# CAN_RS232.net
KiCad netlist of a schematic drawn in Altium Designer
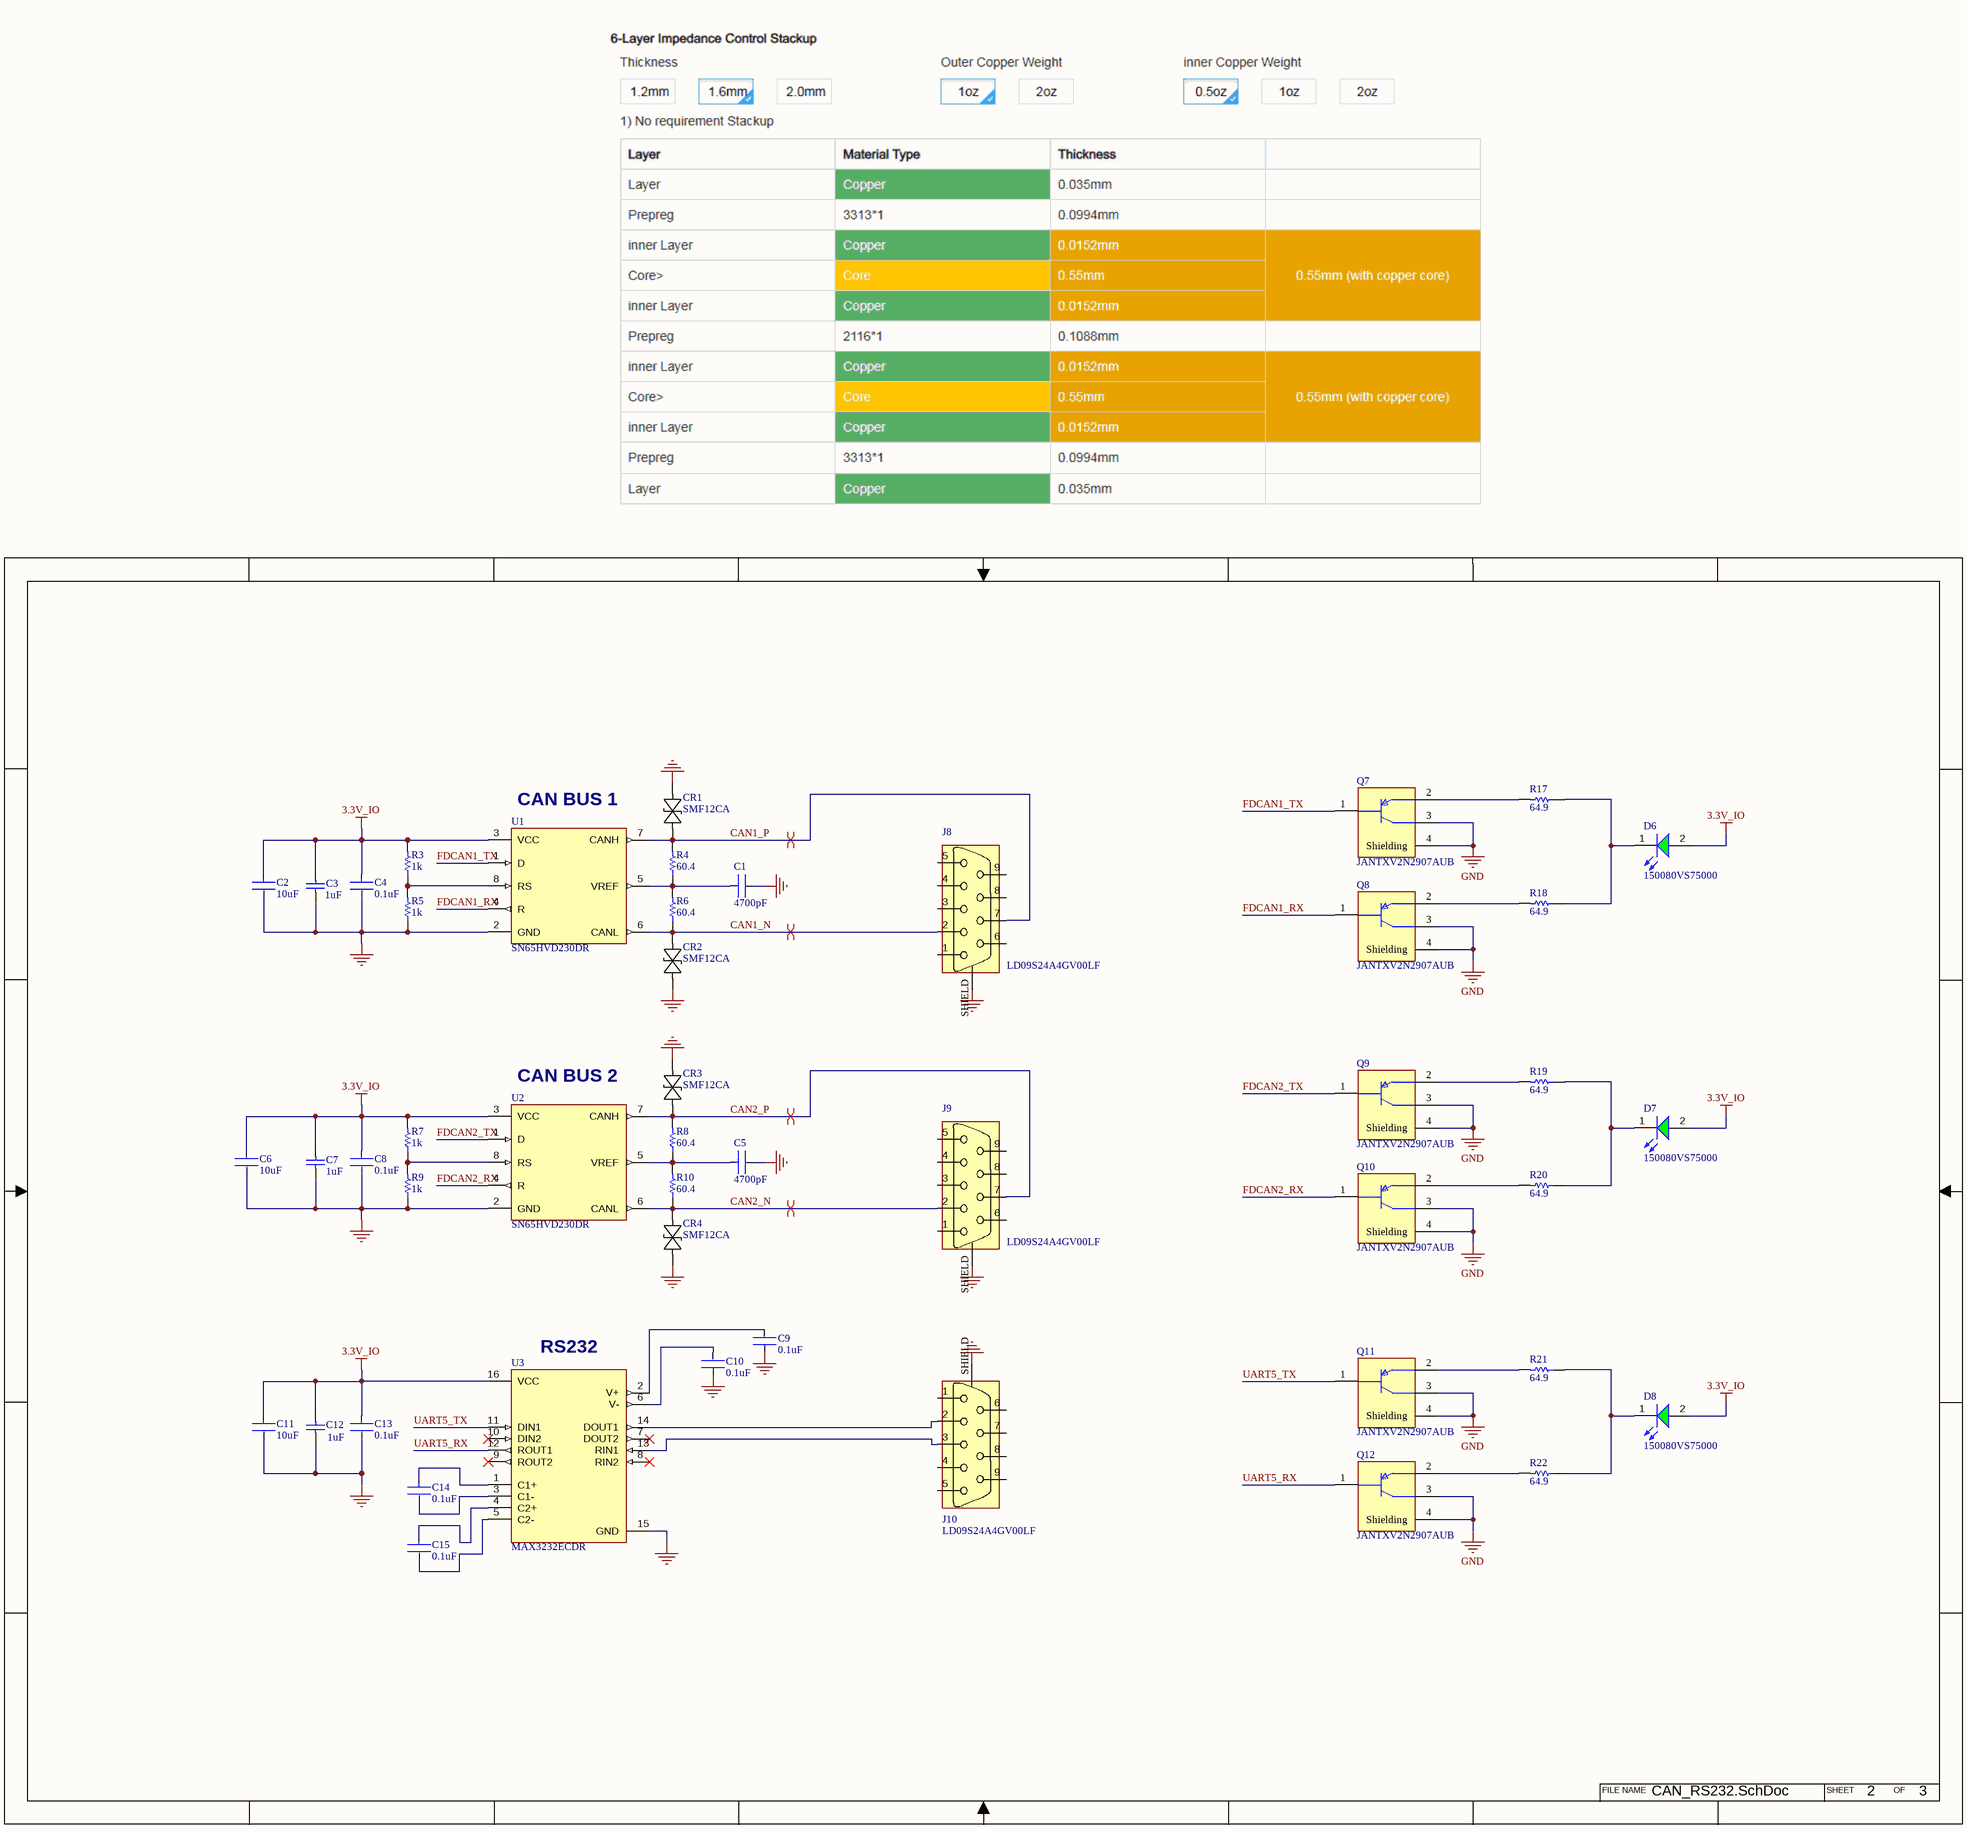
[diagram p0: CAN_RS232.SchDoc]

(export (version "E")
  (design (tool "Eeschema 10.0.6"))
  (components
    (comp (ref "C1")
      (value "4700pF")
      (footprint "FP-CC0805-0_85-MFG")
      (description "CAP CER 4700PF 50V X7R 0805")
      (fields (field (name "TOLERANCE") "0.1") (field (name "MANUFACTURER") "Yageo"))
      (libsource (lib "Altium Content Vault") (part "11868f565c42a9108669ba33697ecf6"))
    )
    (comp (ref "C2")
      (value "10uF")
      (footprint "FP-CL31-IPC_B")
      (description "Cap Ceramic 10uF 25V X7R ±10% SMD 1206 +125°C Embossed T/R")
      (fields (field (name "TOLERANCE") "10%"))
      (libsource (lib "Altium Content Vault") (part "b4654b650e69147ec39a6b967a45e02"))
    )
    (comp (ref "C3")
      (value "1uF")
      (footprint "CAPC2013X100X50ML20T25")
      (description "C0805C105K8RACTU")
      (fields (field (name "MANUFACTURER") "Kemet"))
      (libsource (lib "Altium Content Vault") (part "CAP"))
    )
    (comp (ref "C4")
      (value "0.1uF")
      (footprint "FP-CC0805-0_85-MFG")
      (description "CAP CER 0.1UF 50V X7R 0805")
      (fields (field (name "TOLERANCE") "0.1") (field (name "MANUFACTURER PART NUMBER") "CC0805KRX7R9BB104"))
      (libsource (lib "Altium Content Vault") (part "11868f565c42a9108669ba33697ecf6"))
    )
    (comp (ref "C5")
      (value "4700pF")
      (footprint "FP-CC0805-0_85-MFG")
      (description "CAP CER 4700PF 50V X7R 0805")
      (fields (field (name "TOLERANCE") "0.1") (field (name "MANUFACTURER") "Yageo"))
      (libsource (lib "Altium Content Vault") (part "11868f565c42a9108669ba33697ecf6"))
    )
    (comp (ref "C6")
      (value "10uF")
      (footprint "FP-CL31-IPC_B")
      (description "Cap Ceramic 10uF 25V X7R ±10% SMD 1206 +125°C Embossed T/R")
      (fields (field (name "TOLERANCE") "10%"))
      (libsource (lib "Altium Content Vault") (part "b4654b650e69147ec39a6b967a45e02"))
    )
    (comp (ref "C7")
      (value "1uF")
      (footprint "CAPC2013X100X50ML20T25")
      (fields (field (name "PART NUMBER") "C0805C105K8RACTU") (field (name "MANUFACTURER") "Kemet"))
      (libsource (lib "Altium Content Vault") (part "CAP"))
    )
    (comp (ref "C8")
      (value "0.1uF")
      (footprint "FP-CC0805-0_85-MFG")
      (description "CAP CER 0.1UF 50V X7R 0805")
      (fields (field (name "TOLERANCE") "0.1") (field (name "MANUFACTURER PART NUMBER") "CC0805KRX7R9BB104"))
      (libsource (lib "Altium Content Vault") (part "11868f565c42a9108669ba33697ecf6"))
    )
    (comp (ref "C9")
      (value "0.1uF")
      (footprint "FP-CC0805-0_85-MFG")
      (description "CAP CER 0.1UF 50V X7R 0805")
      (fields (field (name "TOLERANCE") "0.1") (field (name "MANUFACTURER PART NUMBER") "CC0805KRX7R9BB104"))
      (libsource (lib "Altium Content Vault") (part "11868f565c42a9108669ba33697ecf6"))
    )
    (comp (ref "C10")
      (value "0.1uF")
      (footprint "FP-CC0805-0_85-MFG")
      (description "CAP CER 0.1UF 50V X7R 0805")
      (fields (field (name "TOLERANCE") "0.1") (field (name "MANUFACTURER PART NUMBER") "CC0805KRX7R9BB104"))
      (libsource (lib "Altium Content Vault") (part "11868f565c42a9108669ba33697ecf6"))
    )
    (comp (ref "C11")
      (value "10uF")
      (footprint "FP-CL31-IPC_B")
      (description "Cap Ceramic 10uF 25V X7R ±10% SMD 1206 +125°C Embossed T/R")
      (fields (field (name "TOLERANCE") "10%"))
      (libsource (lib "Altium Content Vault") (part "b4654b650e69147ec39a6b967a45e02"))
    )
    (comp (ref "C12")
      (value "1uF")
      (footprint "CAPC2013X100X50ML20T25")
      (fields (field (name "PART NUMBER") "C0805C105K8RACTU") (field (name "MANUFACTURER") "Kemet"))
      (libsource (lib "Altium Content Vault") (part "CAP"))
    )
    (comp (ref "C13")
      (value "0.1uF")
      (footprint "FP-CC0805-0_85-MFG")
      (description "CAP CER 0.1UF 50V X7R 0805")
      (fields (field (name "TOLERANCE") "0.1") (field (name "MANUFACTURER PART NUMBER") "CC0805KRX7R9BB104"))
      (libsource (lib "Altium Content Vault") (part "11868f565c42a9108669ba33697ecf6"))
    )
    (comp (ref "C14")
      (value "0.1uF")
      (footprint "FP-CC0805-0_85-MFG")
      (description "CAP CER 0.1UF 50V X7R 0805")
      (fields (field (name "TOLERANCE") "0.1") (field (name "MANUFACTURER PART NUMBER") "CC0805KRX7R9BB104"))
      (libsource (lib "Altium Content Vault") (part "11868f565c42a9108669ba33697ecf6"))
    )
    (comp (ref "C15")
      (value "0.1uF")
      (footprint "FP-CC0805-0_85-MFG")
      (description "CAP CER 0.1UF 50V X7R 0805")
      (fields (field (name "TOLERANCE") "0.1") (field (name "MANUFACTURER PART NUMBER") "CC0805KRX7R9BB104"))
      (libsource (lib "Altium Content Vault") (part "11868f565c42a9108669ba33697ecf6"))
    )
    (comp (ref "CR1")
      (value "SMF12CA")
      (footprint "SOD-123F_LTF")
      (description "No Description Available")
      (libsource (lib "SMF12CA") (part "SMF12CA"))
    )
    (comp (ref "CR2")
      (value "SMF12CA")
      (footprint "SOD-123F_LTF")
      (description "No Description Available")
      (libsource (lib "SMF12CA") (part "SMF12CA"))
    )
    (comp (ref "CR3")
      (value "SMF12CA")
      (footprint "SOD-123F_LTF")
      (description "No Description Available")
      (libsource (lib "SMF12CA") (part "SMF12CA"))
    )
    (comp (ref "CR4")
      (value "SMF12CA")
      (footprint "SOD-123F_LTF")
      (description "No Description Available")
      (libsource (lib "SMF12CA") (part "SMF12CA"))
    )
    (comp (ref "D6")
      (value "150080VS75000")
      (footprint "WL-SMCW_0805_150080xx75000")
      (description "WL-SMCW SMT Mono-Color Chip LED Waterclear")
      (libsource (lib "Altium Content Vault") (part "LED_Green_2A-1K"))
    )
    (comp (ref "D7")
      (value "150080VS75000")
      (footprint "WL-SMCW_0805_150080xx75000")
      (description "WL-SMCW SMT Mono-Color Chip LED Waterclear")
      (libsource (lib "Altium Content Vault") (part "LED_Green_2A-1K"))
    )
    (comp (ref "D8")
      (value "150080VS75000")
      (footprint "WL-SMCW_0805_150080xx75000")
      (description "WL-SMCW SMT Mono-Color Chip LED Waterclear")
      (libsource (lib "Altium Content Vault") (part "LED_Green_2A-1K"))
    )
    (comp (ref "J8")
      (value "LD09S24A4GV00LF")
      (footprint "ASSMANN_A-DF09A/KG-T2S")
      (description "No Description Available")
      (libsource (lib "LD09S24A4GV00LF") (part "LD09S24A4GV00LF"))
    )
    (comp (ref "J9")
      (value "LD09S24A4GV00LF")
      (footprint "ASSMANN_A-DF09A/KG-T2S")
      (description "No Description Available")
      (libsource (lib "LD09S24A4GV00LF") (part "LD09S24A4GV00LF"))
    )
    (comp (ref "J10")
      (value "LD09S24A4GV00LF")
      (footprint "ASSMANN_A-DF09A/KG-T2S")
      (description "No Description Available")
      (libsource (lib "") (part "LD09S24A4GV00LF_1"))
    )
    (comp (ref "Q7")
      (value "JANTXV2N2907AUB")
      (footprint "FP-UB-IPC_C")
      (description "TRANS PNP 60V 0.6A 4UB")
      (libsource (lib "Altium Content Vault") (part "0d70041905f6d5555c09c601eb40e03"))
    )
    (comp (ref "Q8")
      (value "JANTXV2N2907AUB")
      (footprint "FP-UB-IPC_C")
      (description "TRANS PNP 60V 0.6A 4UB")
      (libsource (lib "Altium Content Vault") (part "0d70041905f6d5555c09c601eb40e03"))
    )
    (comp (ref "Q9")
      (value "JANTXV2N2907AUB")
      (footprint "FP-UB-IPC_C")
      (description "TRANS PNP 60V 0.6A 4UB")
      (libsource (lib "Altium Content Vault") (part "0d70041905f6d5555c09c601eb40e03"))
    )
    (comp (ref "Q10")
      (value "JANTXV2N2907AUB")
      (footprint "FP-UB-IPC_C")
      (description "TRANS PNP 60V 0.6A 4UB")
      (libsource (lib "Altium Content Vault") (part "0d70041905f6d5555c09c601eb40e03"))
    )
    (comp (ref "Q11")
      (value "JANTXV2N2907AUB")
      (footprint "FP-UB-IPC_C")
      (description "TRANS PNP 60V 0.6A 4UB")
      (libsource (lib "Altium Content Vault") (part "0d70041905f6d5555c09c601eb40e03"))
    )
    (comp (ref "Q12")
      (value "JANTXV2N2907AUB")
      (footprint "FP-UB-IPC_C")
      (description "TRANS PNP 60V 0.6A 4UB")
      (libsource (lib "Altium Content Vault") (part "0d70041905f6d5555c09c601eb40e03"))
    )
    (comp (ref "R3")
      (value "1k")
      (footprint "RESC2013X60X35ML10T20")
      (description "Chip Resistor, 1 KOhm, +/- 1%, 125 mW, -55 to 155 degC, 0805 (2012 Metric), RoHS, Tape and Reel")
      (fields (field (name "TOLERANCE") "1%") (field (name "MANUFACTURER") "Yageo"))
      (libsource (lib "Altium Content Vault") (part "RES-2"))
    )
    (comp (ref "R4")
      (value "60.4")
      (footprint "RESC2013X60X35LL10T20")
      (fields (field (name "PART NUMBER") "RC0805FR-0760R4L") (field (name "MANUFACTURER") "Yageo"))
      (libsource (lib "Altium Content Vault") (part "RES"))
    )
    (comp (ref "R5")
      (value "1k")
      (footprint "RESC2013X60X35ML10T20")
      (description "Chip Resistor, 1 KOhm, +/- 1%, 125 mW, -55 to 155 degC, 0805 (2012 Metric), RoHS, Tape and Reel")
      (fields (field (name "TOLERANCE") "1%") (field (name "MANUFACTURER") "Yageo"))
      (libsource (lib "Altium Content Vault") (part "RES-2"))
    )
    (comp (ref "R6")
      (value "60.4")
      (footprint "RESC2013X60X35LL10T20")
      (fields (field (name "PART NUMBER") "RC0805FR-0760R4L") (field (name "MANUFACTURER") "Yageo"))
      (libsource (lib "Altium Content Vault") (part "RES"))
    )
    (comp (ref "R7")
      (value "1k")
      (footprint "RESC2013X60X35ML10T20")
      (description "Chip Resistor, 1 KOhm, +/- 1%, 125 mW, -55 to 155 degC, 0805 (2012 Metric), RoHS, Tape and Reel")
      (fields (field (name "TOLERANCE") "1%") (field (name "MANUFACTURER") "Yageo"))
      (libsource (lib "Altium Content Vault") (part "RES-2"))
    )
    (comp (ref "R8")
      (value "60.4")
      (footprint "RESC2013X60X35LL10T20")
      (fields (field (name "PART NUMBER") "RC0805FR-0760R4L") (field (name "MANUFACTURER") "Yageo"))
      (libsource (lib "Altium Content Vault") (part "RES"))
    )
    (comp (ref "R9")
      (value "1k")
      (footprint "RESC2013X60X35ML10T20")
      (description "Chip Resistor, 1 KOhm, +/- 1%, 125 mW, -55 to 155 degC, 0805 (2012 Metric), RoHS, Tape and Reel")
      (fields (field (name "TOLERANCE") "1%") (field (name "MANUFACTURER") "Yageo"))
      (libsource (lib "Altium Content Vault") (part "RES-2"))
    )
    (comp (ref "R10")
      (value "60.4")
      (footprint "RESC2013X60X35LL10T20")
      (fields (field (name "PART NUMBER") "RC0805FR-0760R4L") (field (name "MANUFACTURER") "Yageo"))
      (libsource (lib "Altium Content Vault") (part "RES"))
    )
    (comp (ref "R17")
      (value "64.9")
      (footprint "RESC2013X60X35LL10T20")
      (fields (field (name "PART NUMBER") "RC0805FR-0764R9L") (field (name "MANUFACTURER") "Yageo"))
      (libsource (lib "Altium Content Vault") (part "RES"))
    )
    (comp (ref "R18")
      (value "64.9")
      (footprint "RESC2013X60X35LL10T20")
      (fields (field (name "PART NUMBER") "RC0805FR-0764R9L") (field (name "MANUFACTURER") "Yageo"))
      (libsource (lib "Altium Content Vault") (part "RES"))
    )
    (comp (ref "R19")
      (value "64.9")
      (footprint "RESC2013X60X35LL10T20")
      (fields (field (name "PART NUMBER") "RC0805FR-0764R9L") (field (name "MANUFACTURER") "Yageo"))
      (libsource (lib "Altium Content Vault") (part "RES"))
    )
    (comp (ref "R20")
      (value "64.9")
      (footprint "RESC2013X60X35LL10T20")
      (fields (field (name "PART NUMBER") "RC0805FR-0764R9L") (field (name "MANUFACTURER") "Yageo"))
      (libsource (lib "Altium Content Vault") (part "RES"))
    )
    (comp (ref "R21")
      (value "64.9")
      (footprint "RESC2013X60X35LL10T20")
      (fields (field (name "PART NUMBER") "RC0805FR-0764R9L") (field (name "MANUFACTURER") "Yageo"))
      (libsource (lib "Altium Content Vault") (part "RES"))
    )
    (comp (ref "R22")
      (value "64.9")
      (footprint "RESC2013X60X35LL10T20")
      (fields (field (name "PART NUMBER") "RC0805FR-0764R9L") (field (name "MANUFACTURER") "Yageo"))
      (libsource (lib "Altium Content Vault") (part "RES"))
    )
    (comp (ref "U1")
      (value "SN65HVD230DR")
      (footprint "SOIC127P599X175-8N")
      (description "3.3 V CAN Transceiver with Standby Mode 8-SOIC -40 to 85")
      (fields (field (name "MF") "Texas Instruments"))
      (libsource (lib "ertc_symbols") (part "SN65HVD230DR"))
    )
    (comp (ref "U2")
      (value "SN65HVD230DR")
      (footprint "SOIC127P599X175-8N")
      (description "3.3 V CAN Transceiver with Standby Mode 8-SOIC -40 to 85")
      (fields (field (name "MF") "Texas Instruments"))
      (libsource (lib "ertc_symbols") (part "SN65HVD230DR"))
    )
    (comp (ref "U3")
      (value "MAX3232ECDR")
      (footprint "SOIC127P600X175-16N:SOIC127P600X175-16N")
      (libsource (lib "MAX3232ECDR") (part "MAX3232ECDR"))
    )
  )
  (nets
    (net (code "1") (name "/CAN1_N") (class "Default")
      (node (ref "CR2") (pin "2") (pinfunction "2_2") (pintype "passive"))
      (node (ref "J8") (pin "2") (pinfunction "2_2") (pintype "passive"))
      (node (ref "R6") (pin "1") (pinfunction "1_1") (pintype "passive"))
      (node (ref "U1") (pin "6") (pinfunction "CANL_6") (pintype "output"))
    )
    (net (code "2") (name "/CAN1_P") (class "Default")
      (node (ref "CR1") (pin "2") (pinfunction "2_2") (pintype "passive"))
      (node (ref "J8") (pin "7") (pinfunction "7_7") (pintype "passive"))
      (node (ref "R4") (pin "2") (pinfunction "2_2") (pintype "passive"))
      (node (ref "U1") (pin "7") (pinfunction "CANH_7") (pintype "output"))
    )
    (net (code "3") (name "/CAN2_N") (class "Default")
      (node (ref "CR4") (pin "1") (pinfunction "1_1") (pintype "passive"))
      (node (ref "J9") (pin "2") (pinfunction "2_2") (pintype "passive"))
      (node (ref "R10") (pin "1") (pinfunction "1_1") (pintype "passive"))
      (node (ref "U2") (pin "6") (pinfunction "CANL_6") (pintype "output"))
    )
    (net (code "4") (name "/CAN2_P") (class "Default")
      (node (ref "CR3") (pin "1") (pinfunction "1_1") (pintype "passive"))
      (node (ref "J9") (pin "7") (pinfunction "7_7") (pintype "passive"))
      (node (ref "R8") (pin "2") (pinfunction "2_2") (pintype "passive"))
      (node (ref "U2") (pin "7") (pinfunction "CANH_7") (pintype "output"))
    )
    (net (code "5") (name "/FDCAN1_RX") (class "Default")
      (node (ref "Q8") (pin "1") (pinfunction "B_1") (pintype "passive"))
      (node (ref "U1") (pin "4") (pinfunction "R_4") (pintype "output"))
    )
    (net (code "6") (name "/FDCAN1_TX") (class "Default")
      (node (ref "Q7") (pin "1") (pinfunction "B_1") (pintype "passive"))
      (node (ref "U1") (pin "1") (pinfunction "D_1") (pintype "input"))
    )
    (net (code "7") (name "/FDCAN2_RX") (class "Default")
      (node (ref "Q10") (pin "1") (pinfunction "B_1") (pintype "passive"))
      (node (ref "U2") (pin "4") (pinfunction "R_4") (pintype "output"))
    )
    (net (code "8") (name "/FDCAN2_TX") (class "Default")
      (node (ref "Q9") (pin "1") (pinfunction "B_1") (pintype "passive"))
      (node (ref "U2") (pin "1") (pinfunction "D_1") (pintype "input"))
    )
    (net (code "9") (name "/UART5_RX") (class "Default")
      (node (ref "Q12") (pin "1") (pinfunction "B_1") (pintype "passive"))
      (node (ref "U3") (pin "12") (pinfunction "ROUT1_12") (pintype "output"))
    )
    (net (code "10") (name "/UART5_TX") (class "Default")
      (node (ref "Q11") (pin "1") (pinfunction "B_1") (pintype "passive"))
      (node (ref "U3") (pin "11") (pinfunction "DIN1_11") (pintype "input"))
    )
    (net (code "11") (name "3.3V_IO") (class "Default")
      (node (ref "C11") (pin "1") (pinfunction "1_1") (pintype "passive"))
      (node (ref "C12") (pin "2") (pinfunction "2_2") (pintype "passive"))
      (node (ref "C13") (pin "1") (pinfunction "1_1") (pintype "passive"))
      (node (ref "C2") (pin "1") (pinfunction "1_1") (pintype "passive"))
      (node (ref "C3") (pin "2") (pinfunction "2_2") (pintype "passive"))
      (node (ref "C4") (pin "1") (pinfunction "1_1") (pintype "passive"))
      (node (ref "C6") (pin "1") (pinfunction "1_1") (pintype "passive"))
      (node (ref "C7") (pin "2") (pinfunction "2_2") (pintype "passive"))
      (node (ref "C8") (pin "1") (pinfunction "1_1") (pintype "passive"))
      (node (ref "D6") (pin "2") (pinfunction "A_2") (pintype "passive"))
      (node (ref "D7") (pin "2") (pinfunction "A_2") (pintype "passive"))
      (node (ref "D8") (pin "2") (pinfunction "A_2") (pintype "passive"))
      (node (ref "R3") (pin "2") (pinfunction "2_2") (pintype "passive"))
      (node (ref "R7") (pin "2") (pinfunction "2_2") (pintype "passive"))
      (node (ref "U1") (pin "3") (pinfunction "VCC_3") (pintype "power_in"))
      (node (ref "U2") (pin "3") (pinfunction "VCC_3") (pintype "power_in"))
      (node (ref "U3") (pin "16") (pinfunction "VCC_16") (pintype "power_in"))
    )
    (net (code "12") (name "GND") (class "Default")
      (node (ref "C1") (pin "2") (pinfunction "2_2") (pintype "passive"))
      (node (ref "C10") (pin "1") (pinfunction "1_1") (pintype "passive"))
      (node (ref "C11") (pin "2") (pinfunction "2_2") (pintype "passive"))
      (node (ref "C12") (pin "1") (pinfunction "1_1") (pintype "passive"))
      (node (ref "C13") (pin "2") (pinfunction "2_2") (pintype "passive"))
      (node (ref "C2") (pin "2") (pinfunction "2_2") (pintype "passive"))
      (node (ref "C3") (pin "1") (pinfunction "1_1") (pintype "passive"))
      (node (ref "C4") (pin "2") (pinfunction "2_2") (pintype "passive"))
      (node (ref "C5") (pin "2") (pinfunction "2_2") (pintype "passive"))
      (node (ref "C6") (pin "2") (pinfunction "2_2") (pintype "passive"))
      (node (ref "C7") (pin "1") (pinfunction "1_1") (pintype "passive"))
      (node (ref "C8") (pin "2") (pinfunction "2_2") (pintype "passive"))
      (node (ref "C9") (pin "1") (pinfunction "1_1") (pintype "passive"))
      (node (ref "CR1") (pin "1") (pinfunction "1_1") (pintype "passive"))
      (node (ref "CR2") (pin "1") (pinfunction "1_1") (pintype "passive"))
      (node (ref "CR3") (pin "2") (pinfunction "2_2") (pintype "passive"))
      (node (ref "CR4") (pin "2") (pinfunction "2_2") (pintype "passive"))
      (node (ref "J10") (pin "SHIELD") (pinfunction "SHIELD_SHIELD") (pintype "passive"))
      (node (ref "J8") (pin "SHIELD") (pinfunction "SHIELD_SHIELD") (pintype "passive"))
      (node (ref "J9") (pin "SHIELD") (pinfunction "SHIELD_SHIELD") (pintype "passive"))
      (node (ref "Q10") (pin "3") (pinfunction "C_3") (pintype "passive"))
      (node (ref "Q10") (pin "4") (pinfunction "Shielding_4") (pintype "passive"))
      (node (ref "Q11") (pin "3") (pinfunction "C_3") (pintype "passive"))
      (node (ref "Q11") (pin "4") (pinfunction "Shielding_4") (pintype "passive"))
      (node (ref "Q12") (pin "3") (pinfunction "C_3") (pintype "passive"))
      (node (ref "Q12") (pin "4") (pinfunction "Shielding_4") (pintype "passive"))
      (node (ref "Q7") (pin "3") (pinfunction "C_3") (pintype "passive"))
      (node (ref "Q7") (pin "4") (pinfunction "Shielding_4") (pintype "passive"))
      (node (ref "Q8") (pin "3") (pinfunction "C_3") (pintype "passive"))
      (node (ref "Q8") (pin "4") (pinfunction "Shielding_4") (pintype "passive"))
      (node (ref "Q9") (pin "3") (pinfunction "C_3") (pintype "passive"))
      (node (ref "Q9") (pin "4") (pinfunction "Shielding_4") (pintype "passive"))
      (node (ref "R5") (pin "1") (pinfunction "1_1") (pintype "passive"))
      (node (ref "R9") (pin "1") (pinfunction "1_1") (pintype "passive"))
      (node (ref "U1") (pin "2") (pinfunction "GND_2") (pintype "power_in"))
      (node (ref "U2") (pin "2") (pinfunction "GND_2") (pintype "power_in"))
      (node (ref "U3") (pin "15") (pinfunction "GND_15") (pintype "power_in"))
    )
    (net (code "13") (name "Net-(D6-K)") (class "Default")
      (node (ref "D6") (pin "1") (pinfunction "K_1") (pintype "passive"))
      (node (ref "R17") (pin "1") (pinfunction "1_1") (pintype "passive"))
      (node (ref "R18") (pin "1") (pinfunction "1_1") (pintype "passive"))
    )
    (net (code "14") (name "Net-(D7-K)") (class "Default")
      (node (ref "D7") (pin "1") (pinfunction "K_1") (pintype "passive"))
      (node (ref "R19") (pin "1") (pinfunction "1_1") (pintype "passive"))
      (node (ref "R20") (pin "1") (pinfunction "1_1") (pintype "passive"))
    )
    (net (code "15") (name "Net-(D8-K)") (class "Default")
      (node (ref "D8") (pin "1") (pinfunction "K_1") (pintype "passive"))
      (node (ref "R21") (pin "1") (pinfunction "1_1") (pintype "passive"))
      (node (ref "R22") (pin "1") (pinfunction "1_1") (pintype "passive"))
    )
    (net (code "16") (name "Net-(Q7-E)") (class "Default")
      (node (ref "Q7") (pin "2") (pinfunction "E_2") (pintype "passive"))
      (node (ref "R17") (pin "2") (pinfunction "2_2") (pintype "passive"))
    )
    (net (code "17") (name "Net-(Q8-E)") (class "Default")
      (node (ref "Q8") (pin "2") (pinfunction "E_2") (pintype "passive"))
      (node (ref "R18") (pin "2") (pinfunction "2_2") (pintype "passive"))
    )
    (net (code "18") (name "Net-(Q9-E)") (class "Default")
      (node (ref "Q9") (pin "2") (pinfunction "E_2") (pintype "passive"))
      (node (ref "R19") (pin "2") (pinfunction "2_2") (pintype "passive"))
    )
    (net (code "19") (name "Net-(Q10-E)") (class "Default")
      (node (ref "Q10") (pin "2") (pinfunction "E_2") (pintype "passive"))
      (node (ref "R20") (pin "2") (pinfunction "2_2") (pintype "passive"))
    )
    (net (code "20") (name "Net-(Q11-E)") (class "Default")
      (node (ref "Q11") (pin "2") (pinfunction "E_2") (pintype "passive"))
      (node (ref "R21") (pin "2") (pinfunction "2_2") (pintype "passive"))
    )
    (net (code "21") (name "Net-(Q12-E)") (class "Default")
      (node (ref "Q12") (pin "2") (pinfunction "E_2") (pintype "passive"))
      (node (ref "R22") (pin "2") (pinfunction "2_2") (pintype "passive"))
    )
    (net (code "22") (name "Net-(U1-RS)") (class "Default")
      (node (ref "R3") (pin "1") (pinfunction "1_1") (pintype "passive"))
      (node (ref "R5") (pin "2") (pinfunction "2_2") (pintype "passive"))
      (node (ref "U1") (pin "8") (pinfunction "RS_8") (pintype "input"))
    )
    (net (code "23") (name "Net-(U1-VREF)") (class "Default")
      (node (ref "C1") (pin "1") (pinfunction "1_1") (pintype "passive"))
      (node (ref "R4") (pin "1") (pinfunction "1_1") (pintype "passive"))
      (node (ref "R6") (pin "2") (pinfunction "2_2") (pintype "passive"))
      (node (ref "U1") (pin "5") (pinfunction "VREF_5") (pintype "output"))
    )
    (net (code "24") (name "Net-(U2-RS)") (class "Default")
      (node (ref "R7") (pin "1") (pinfunction "1_1") (pintype "passive"))
      (node (ref "R9") (pin "2") (pinfunction "2_2") (pintype "passive"))
      (node (ref "U2") (pin "8") (pinfunction "RS_8") (pintype "input"))
    )
    (net (code "25") (name "Net-(U2-VREF)") (class "Default")
      (node (ref "C5") (pin "1") (pinfunction "1_1") (pintype "passive"))
      (node (ref "R10") (pin "2") (pinfunction "2_2") (pintype "passive"))
      (node (ref "R8") (pin "1") (pinfunction "1_1") (pintype "passive"))
      (node (ref "U2") (pin "5") (pinfunction "VREF_5") (pintype "output"))
    )
    (net (code "26") (name "Net-(U3-C1+)") (class "Default")
      (node (ref "C14") (pin "1") (pinfunction "1_1") (pintype "passive"))
      (node (ref "U3") (pin "1") (pinfunction "C1+_1") (pintype "passive"))
    )
    (net (code "27") (name "Net-(U3-C1-)") (class "Default")
      (node (ref "C14") (pin "2") (pinfunction "2_2") (pintype "passive"))
      (node (ref "U3") (pin "3") (pinfunction "C1-_3") (pintype "passive"))
    )
    (net (code "28") (name "Net-(U3-C2+)") (class "Default")
      (node (ref "C15") (pin "1") (pinfunction "1_1") (pintype "passive"))
      (node (ref "U3") (pin "4") (pinfunction "C2+_4") (pintype "passive"))
    )
    (net (code "29") (name "Net-(U3-C2-)") (class "Default")
      (node (ref "C15") (pin "2") (pinfunction "2_2") (pintype "passive"))
      (node (ref "U3") (pin "5") (pinfunction "C2-_5") (pintype "passive"))
    )
    (net (code "30") (name "Net-(U3-DOUT1)") (class "Default")
      (node (ref "J10") (pin "2") (pinfunction "2_2") (pintype "passive"))
      (node (ref "U3") (pin "14") (pinfunction "DOUT1_14") (pintype "output"))
    )
    (net (code "31") (name "Net-(U3-RIN1)") (class "Default")
      (node (ref "J10") (pin "3") (pinfunction "3_3") (pintype "passive"))
      (node (ref "U3") (pin "13") (pinfunction "RIN1_13") (pintype "input"))
    )
    (net (code "32") (name "Net-(U3-V+)") (class "Default")
      (node (ref "C9") (pin "2") (pinfunction "2_2") (pintype "passive"))
      (node (ref "U3") (pin "2") (pinfunction "V+_2") (pintype "output"))
    )
    (net (code "33") (name "Net-(U3-V-)") (class "Default")
      (node (ref "C10") (pin "2") (pinfunction "2_2") (pintype "passive"))
      (node (ref "U3") (pin "6") (pinfunction "V-_6") (pintype "output"))
    )
    (net (code "34") (name "unconnected-(J8-Pad1)") (class "Default")
      (node (ref "J8") (pin "1") (pinfunction "1_1") (pintype "passive"))
    )
    (net (code "35") (name "unconnected-(J8-Pad3)") (class "Default")
      (node (ref "J8") (pin "3") (pinfunction "3_3") (pintype "passive"))
    )
    (net (code "36") (name "unconnected-(J8-Pad4)") (class "Default")
      (node (ref "J8") (pin "4") (pinfunction "4_4") (pintype "passive"))
    )
    (net (code "37") (name "unconnected-(J8-Pad5)") (class "Default")
      (node (ref "J8") (pin "5") (pinfunction "5_5") (pintype "passive"))
    )
    (net (code "38") (name "unconnected-(J8-Pad6)") (class "Default")
      (node (ref "J8") (pin "6") (pinfunction "6_6") (pintype "passive"))
    )
    (net (code "39") (name "unconnected-(J8-Pad8)") (class "Default")
      (node (ref "J8") (pin "8") (pinfunction "8_8") (pintype "passive"))
    )
    (net (code "40") (name "unconnected-(J8-Pad9)") (class "Default")
      (node (ref "J8") (pin "9") (pinfunction "9_9") (pintype "passive"))
    )
    (net (code "41") (name "unconnected-(J9-Pad1)") (class "Default")
      (node (ref "J9") (pin "1") (pinfunction "1_1") (pintype "passive"))
    )
    (net (code "42") (name "unconnected-(J9-Pad3)") (class "Default")
      (node (ref "J9") (pin "3") (pinfunction "3_3") (pintype "passive"))
    )
    (net (code "43") (name "unconnected-(J9-Pad4)") (class "Default")
      (node (ref "J9") (pin "4") (pinfunction "4_4") (pintype "passive"))
    )
    (net (code "44") (name "unconnected-(J9-Pad5)") (class "Default")
      (node (ref "J9") (pin "5") (pinfunction "5_5") (pintype "passive"))
    )
    (net (code "45") (name "unconnected-(J9-Pad6)") (class "Default")
      (node (ref "J9") (pin "6") (pinfunction "6_6") (pintype "passive"))
    )
    (net (code "46") (name "unconnected-(J9-Pad8)") (class "Default")
      (node (ref "J9") (pin "8") (pinfunction "8_8") (pintype "passive"))
    )
    (net (code "47") (name "unconnected-(J9-Pad9)") (class "Default")
      (node (ref "J9") (pin "9") (pinfunction "9_9") (pintype "passive"))
    )
    (net (code "48") (name "unconnected-(J10-Pad1)") (class "Default")
      (node (ref "J10") (pin "1") (pinfunction "1_1") (pintype "passive"))
    )
    (net (code "49") (name "unconnected-(J10-Pad4)") (class "Default")
      (node (ref "J10") (pin "4") (pinfunction "4_4") (pintype "passive"))
    )
    (net (code "50") (name "unconnected-(J10-Pad5)") (class "Default")
      (node (ref "J10") (pin "5") (pinfunction "5_5") (pintype "passive"))
    )
    (net (code "51") (name "unconnected-(J10-Pad6)") (class "Default")
      (node (ref "J10") (pin "6") (pinfunction "6_6") (pintype "passive"))
    )
    (net (code "52") (name "unconnected-(J10-Pad7)") (class "Default")
      (node (ref "J10") (pin "7") (pinfunction "7_7") (pintype "passive"))
    )
    (net (code "53") (name "unconnected-(J10-Pad8)") (class "Default")
      (node (ref "J10") (pin "8") (pinfunction "8_8") (pintype "passive"))
    )
    (net (code "54") (name "unconnected-(J10-Pad9)") (class "Default")
      (node (ref "J10") (pin "9") (pinfunction "9_9") (pintype "passive"))
    )
    (net (code "55") (name "unconnected-(U3-DIN2-Pad10)") (class "Default")
      (node (ref "U3") (pin "10") (pinfunction "DIN2_10") (pintype "input+no_connect"))
    )
    (net (code "56") (name "unconnected-(U3-DOUT2-Pad7)") (class "Default")
      (node (ref "U3") (pin "7") (pinfunction "DOUT2_7") (pintype "output+no_connect"))
    )
    (net (code "57") (name "unconnected-(U3-RIN2-Pad8)") (class "Default")
      (node (ref "U3") (pin "8") (pinfunction "RIN2_8") (pintype "input+no_connect"))
    )
    (net (code "58") (name "unconnected-(U3-ROUT2-Pad9)") (class "Default")
      (node (ref "U3") (pin "9") (pinfunction "ROUT2_9") (pintype "output+no_connect"))
    )
  )
)
